# Canhbaochayrung.net
KiCad netlist of a schematic drawn in Altium Designer
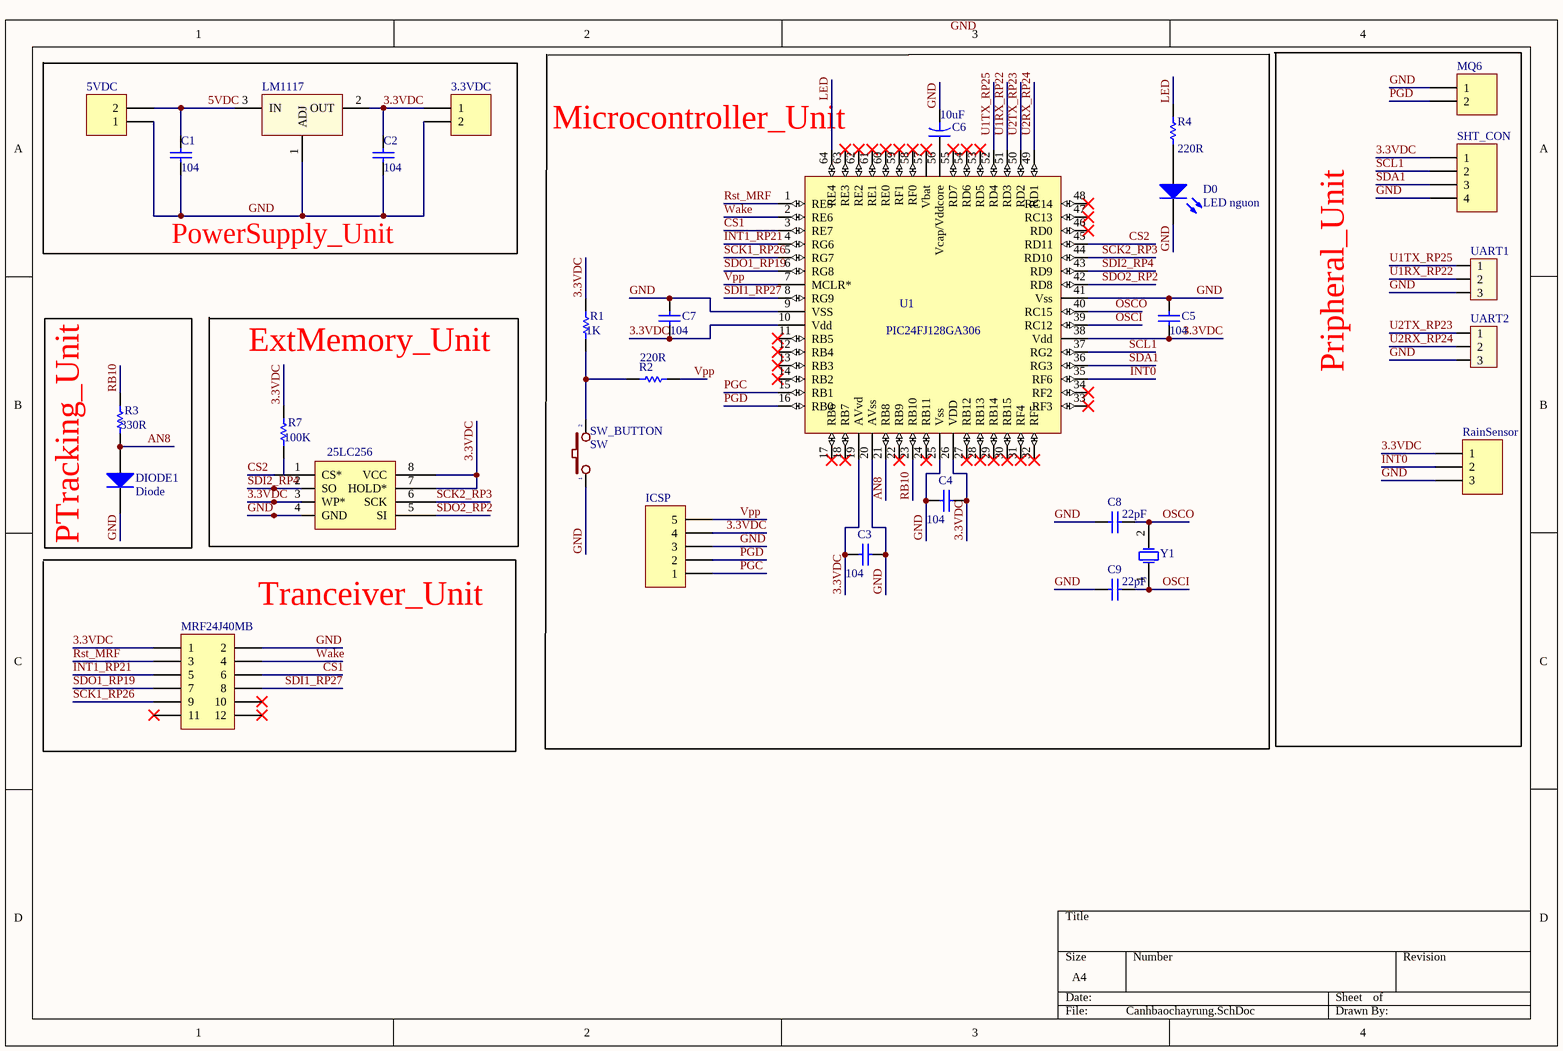
[diagram p0: Canhbaochayrung.SchDoc]

(export (version "E")
  (design (tool "Eeschema 10.0.6"))
  (components
    (comp (ref "3.3VDC")
      (value "Header 2")
      (footprint "HDR1X2")
      (description "Header, 2-Pin")
      (fields (field (name "PUBLISHER") "Altium Limited"))
      (libsource (lib "Miscellaneous Connectors") (part "Header 2"))
    )
    (comp (ref "5VDC")
      (value "Header 2")
      (footprint "HDR1X2")
      (description "Header, 2-Pin")
      (fields (field (name "PUBLISHER") "Altium Limited"))
      (libsource (lib "") (part "Header 2_1"))
    )
    (comp (ref "25LC256") (value "25LC256") (footprint "DIP-8") (libsource (lib "25LC256") (part "25LC256")))
    (comp (ref "C1")
      (value "104")
      (footprint "C0805")
      (description "Capacitor")
      (fields (field (name "Comment") "Cap") (field (name "PUBLISHER") "Altium Limited"))
      (libsource (lib "Miscellaneous Devices") (part "Cap"))
    )
    (comp (ref "C2")
      (value "104")
      (footprint "C0805")
      (description "Capacitor")
      (fields (field (name "Comment") "Cap") (field (name "PUBLISHER") "Altium Limited"))
      (libsource (lib "Miscellaneous Devices") (part "Cap"))
    )
    (comp (ref "C3")
      (value "104")
      (footprint "C0805")
      (description "Capacitor")
      (fields (field (name "Comment") "Cap") (field (name "PUBLISHER") "Altium Limited"))
      (libsource (lib "Miscellaneous Devices") (part "Cap"))
    )
    (comp (ref "C4")
      (value "104")
      (footprint "C0805")
      (description "Capacitor")
      (fields (field (name "Comment") "Cap") (field (name "PUBLISHER") "Altium Limited"))
      (libsource (lib "Miscellaneous Devices") (part "Cap"))
    )
    (comp (ref "C5")
      (value "104")
      (footprint "C0805")
      (description "Capacitor")
      (fields (field (name "Comment") "Cap") (field (name "PUBLISHER") "Altium Limited"))
      (libsource (lib "Miscellaneous Devices") (part "Cap"))
    )
    (comp (ref "C6")
      (value "10uF")
      (footprint "CAP P 6.3x5.4")
      (description "Capacitor")
      (fields (field (name "Comment") "Cap2") (field (name "PUBLISHER") "Altium Limited"))
      (libsource (lib "Miscellaneous Devices") (part "Cap2"))
    )
    (comp (ref "C7")
      (value "104")
      (footprint "C0805")
      (description "Capacitor")
      (fields (field (name "Comment") "Cap") (field (name "PUBLISHER") "Altium Limited"))
      (libsource (lib "Miscellaneous Devices") (part "Cap"))
    )
    (comp (ref "C8")
      (value "22pF")
      (footprint "SM-0805")
      (description "Capacitor")
      (fields (field (name "Comment") "Cap") (field (name "PUBLISHER") "Altium Limited"))
      (libsource (lib "Miscellaneous Devices") (part "Cap"))
    )
    (comp (ref "C9")
      (value "22pF")
      (footprint "SM-0805")
      (description "Capacitor")
      (fields (field (name "Comment") "Cap") (field (name "PUBLISHER") "Altium Limited"))
      (libsource (lib "Miscellaneous Devices") (part "Cap"))
    )
    (comp (ref "D0")
      (value "LED nguon")
      (footprint "LED3mm")
      (description "Typical INFRARED GaAs LED")
      (fields (field (name "PUBLISHER") "Altium Limited"))
      (libsource (lib "Miscellaneous Devices") (part "LED0"))
    )
    (comp (ref "DIODE1")
      (value "Diode")
      (footprint "DZ0.5A")
      (description "Default Diode")
      (fields (field (name "PUBLISHER") "Altium Limited"))
      (libsource (lib "Miscellaneous Devices") (part "Diode"))
    )
    (comp (ref "ICSP")
      (value "ICSP")
      (footprint "CON5")
      (description "Header, 5-Pin")
      (fields (field (name "PUBLISHER") "Altium Limited"))
      (libsource (lib "Miscellaneous Connectors") (part "Header 5"))
    )
    (comp (ref "LM1117")
      (value "LM317")
      (footprint "SOT223-4N")
      (description "Adj Voltage +1.2 -> +37V")
      (libsource (lib "syhaunguyen") (part "LM317"))
    )
    (comp (ref "MQ6")
      (value "MQ-6")
      (footprint "CON2")
      (description "Header, 2-Pin")
      (fields (field (name "PUBLISHER") "Altium Limited"))
      (libsource (lib "Miscellaneous Connectors") (part "Header 2"))
    )
    (comp (ref "MRF24J40MB")
      (value "Header 6X2")
      (footprint "MRF24J40MB_board_mini")
      (description "Header, 6-Pin, Dual row")
      (fields (field (name "PUBLISHER") "Altium Limited"))
      (libsource (lib "Miscellaneous Connectors") (part "Header 6X2"))
    )
    (comp (ref "R1")
      (value "1K")
      (footprint "C0805")
      (description "Resistor")
      (fields (field (name "Comment") "Res1") (field (name "PUBLISHER") "Altium Limited"))
      (libsource (lib "Miscellaneous Devices") (part "Res1"))
    )
    (comp (ref "R2")
      (value "220R")
      (footprint "C0805")
      (description "Resistor")
      (fields (field (name "Comment") "res") (field (name "PUBLISHER") "Altium Limited"))
      (libsource (lib "Miscellaneous Devices") (part "Res1"))
    )
    (comp (ref "R3")
      (value "330R")
      (footprint "C0805")
      (description "Resistor")
      (fields (field (name "Comment") "Res1") (field (name "PUBLISHER") "Altium Limited"))
      (libsource (lib "Miscellaneous Devices") (part "Res1"))
    )
    (comp (ref "R4")
      (value "220R")
      (footprint "C0805")
      (description "Resistor")
      (fields (field (name "Comment") "Res1") (field (name "PUBLISHER") "Altium Limited"))
      (libsource (lib "Miscellaneous Devices") (part "Res1"))
    )
    (comp (ref "R7")
      (value "100K")
      (footprint "C0805")
      (description "Semiconductor Resistor")
      (fields (field (name "Comment") "Res Semi") (field (name "PUBLISHER") "Altium Limited"))
      (libsource (lib "Miscellaneous Devices") (part "Res Semi"))
    )
    (comp (ref "RainSensor")
      (value "PIR module")
      (footprint "CON3")
      (description "Header, 3-Pin, Right Angle")
      (fields (field (name "PUBLISHER") "Altium Limited"))
      (libsource (lib "Miscellaneous Connectors") (part "Header 3H"))
    )
    (comp (ref "SHT_CON")
      (value "SHT10 conector")
      (footprint "CON4")
      (description "Header, 4-Pin")
      (fields (field (name "PUBLISHER") "Altium Limited"))
      (libsource (lib "Miscellaneous Connectors") (part "Header 4"))
    )
    (comp (ref "SW_BUTTON")
      (value "SW")
      (footprint "SW-2P-S")
      (description "Switch button 2 pin")
      (libsource (lib "syhaunguyen") (part "SW2"))
    )
    (comp (ref "U1")
      (value "PIC24FJ128GA306")
      (footprint "TQFP-PT64_N")
      (libsource (lib "Mylibbrary") (part "PIC24FJ128GA306"))
    )
    (comp (ref "UART1")
      (value "UART1")
      (footprint "CON3")
      (description "Connector 3")
      (libsource (lib "syhaunguyen") (part "Con3"))
    )
    (comp (ref "UART2")
      (value "UART2")
      (footprint "CON3")
      (description "Connector 3")
      (libsource (lib "syhaunguyen") (part "Con3"))
    )
    (comp (ref "Y1")
      (value "XTAL")
      (footprint "XT2")
      (description "Crystal Oscillator")
      (fields (field (name "PUBLISHER") "Altium Limited"))
      (libsource (lib "Miscellaneous Devices") (part "XTAL"))
    )
  )
  (nets
    (net (code "1") (name "/3.3VDC") (class "Default")
      (node (ref "25LC256") (pin "3") (pinfunction "WP*_3") (pintype "passive"))
      (node (ref "25LC256") (pin "7") (pinfunction "HOLD*_7") (pintype "passive"))
      (node (ref "25LC256") (pin "8") (pinfunction "VCC_8") (pintype "power_in"))
      (node (ref "3.3VDC") (pin "1") (pinfunction "1_1") (pintype "passive"))
      (node (ref "C2") (pin "2") (pinfunction "2_2") (pintype "passive"))
      (node (ref "C3") (pin "1") (pinfunction "1_1") (pintype "passive"))
      (node (ref "C4") (pin "2") (pinfunction "2_2") (pintype "passive"))
      (node (ref "C5") (pin "1") (pinfunction "1_1") (pintype "passive"))
      (node (ref "C7") (pin "1") (pinfunction "1_1") (pintype "passive"))
      (node (ref "ICSP") (pin "4") (pinfunction "4_4") (pintype "passive"))
      (node (ref "LM1117") (pin "2") (pinfunction "OUT_2") (pintype "passive"))
      (node (ref "MRF24J40MB") (pin "1") (pinfunction "1_1") (pintype "passive"))
      (node (ref "R1") (pin "2") (pinfunction "2_2") (pintype "passive"))
      (node (ref "R7") (pin "2") (pinfunction "2_2") (pintype "passive"))
      (node (ref "RainSensor") (pin "1") (pinfunction "1_1") (pintype "passive"))
      (node (ref "SHT_CON") (pin "1") (pinfunction "1_1") (pintype "passive"))
      (node (ref "U1") (pin "10") (pinfunction "Vdd_10") (pintype "passive"))
      (node (ref "U1") (pin "19") (pinfunction "AVvd_19") (pintype "power_in"))
      (node (ref "U1") (pin "26") (pinfunction "VDD_26") (pintype "power_in"))
      (node (ref "U1") (pin "38") (pinfunction "Vdd_38") (pintype "power_in"))
    )
    (net (code "2") (name "/5VDC") (class "Default")
      (node (ref "5VDC") (pin "2") (pinfunction "2_2") (pintype "passive"))
      (node (ref "C1") (pin "2") (pinfunction "2_2") (pintype "passive"))
      (node (ref "LM1117") (pin "3") (pinfunction "IN_3") (pintype "passive"))
    )
    (net (code "3") (name "/AN8") (class "Default")
      (node (ref "DIODE1") (pin "1") (pinfunction "A_1") (pintype "passive"))
      (node (ref "R3") (pin "1") (pinfunction "1_1") (pintype "passive"))
      (node (ref "U1") (pin "21") (pinfunction "RB8_21") (pintype "bidirectional"))
    )
    (net (code "4") (name "/CS1") (class "Default")
      (node (ref "MRF24J40MB") (pin "6") (pinfunction "6_6") (pintype "passive"))
      (node (ref "U1") (pin "3") (pinfunction "RE7_3") (pintype "bidirectional"))
    )
    (net (code "5") (name "/CS2") (class "Default")
      (node (ref "25LC256") (pin "1") (pinfunction "CS*_1") (pintype "passive"))
      (node (ref "U1") (pin "45") (pinfunction "RD11_45") (pintype "bidirectional"))
    )
    (net (code "6") (name "/GND") (class "Default")
      (node (ref "25LC256") (pin "4") (pinfunction "GND_4") (pintype "power_in"))
      (node (ref "3.3VDC") (pin "2") (pinfunction "2_2") (pintype "passive"))
      (node (ref "5VDC") (pin "1") (pinfunction "1_1") (pintype "passive"))
      (node (ref "C1") (pin "1") (pinfunction "1_1") (pintype "passive"))
      (node (ref "C2") (pin "1") (pinfunction "1_1") (pintype "passive"))
      (node (ref "C3") (pin "2") (pinfunction "2_2") (pintype "passive"))
      (node (ref "C4") (pin "1") (pinfunction "1_1") (pintype "passive"))
      (node (ref "C5") (pin "2") (pinfunction "2_2") (pintype "passive"))
      (node (ref "C6") (pin "2") (pinfunction "2_2") (pintype "passive"))
      (node (ref "C7") (pin "2") (pinfunction "2_2") (pintype "passive"))
      (node (ref "C8") (pin "1") (pinfunction "1_1") (pintype "passive"))
      (node (ref "C9") (pin "1") (pinfunction "1_1") (pintype "passive"))
      (node (ref "D0") (pin "2") (pinfunction "K_2") (pintype "passive"))
      (node (ref "DIODE1") (pin "2") (pinfunction "K_2") (pintype "passive"))
      (node (ref "ICSP") (pin "3") (pinfunction "3_3") (pintype "passive"))
      (node (ref "LM1117") (pin "1") (pinfunction "ADJ_1") (pintype "passive"))
      (node (ref "MQ6") (pin "1") (pinfunction "1_1") (pintype "passive"))
      (node (ref "MRF24J40MB") (pin "2") (pinfunction "2_2") (pintype "passive"))
      (node (ref "RainSensor") (pin "3") (pinfunction "3_3") (pintype "passive"))
      (node (ref "SHT_CON") (pin "4") (pinfunction "4_4") (pintype "passive"))
      (node (ref "SW_BUTTON") (pin "1") (pinfunction "1_1") (pintype "passive"))
      (node (ref "U1") (pin "20") (pinfunction "AVss_20") (pintype "power_in"))
      (node (ref "U1") (pin "25") (pinfunction "Vss_25") (pintype "power_in"))
      (node (ref "U1") (pin "41") (pinfunction "Vss_41") (pintype "power_in"))
      (node (ref "U1") (pin "9") (pinfunction "VSS_9") (pintype "power_in"))
      (node (ref "UART1") (pin "3") (pinfunction "3_3") (pintype "passive"))
      (node (ref "UART2") (pin "3") (pinfunction "3_3") (pintype "passive"))
    )
    (net (code "7") (name "/INT0") (class "Default")
      (node (ref "RainSensor") (pin "2") (pinfunction "2_2") (pintype "passive"))
      (node (ref "U1") (pin "35") (pinfunction "RF6_35") (pintype "bidirectional"))
    )
    (net (code "8") (name "/INT1_RP21") (class "Default")
      (node (ref "MRF24J40MB") (pin "5") (pinfunction "5_5") (pintype "passive"))
      (node (ref "U1") (pin "4") (pinfunction "RG6_4") (pintype "bidirectional"))
    )
    (net (code "9") (name "/LED") (class "Default")
      (node (ref "R4") (pin "2") (pinfunction "2_2") (pintype "passive"))
      (node (ref "U1") (pin "64") (pinfunction "RE4_64") (pintype "bidirectional"))
    )
    (net (code "10") (name "/OSCI") (class "Default")
      (node (ref "C9") (pin "2") (pinfunction "2_2") (pintype "passive"))
      (node (ref "U1") (pin "39") (pinfunction "RC12_39") (pintype "bidirectional"))
      (node (ref "Y1") (pin "1") (pinfunction "OSC1_1") (pintype "passive"))
    )
    (net (code "11") (name "/OSCO") (class "Default")
      (node (ref "C8") (pin "2") (pinfunction "2_2") (pintype "passive"))
      (node (ref "U1") (pin "40") (pinfunction "RC15_40") (pintype "bidirectional"))
      (node (ref "Y1") (pin "2") (pinfunction "OSC2_2") (pintype "passive"))
    )
    (net (code "12") (name "/PGC") (class "Default")
      (node (ref "ICSP") (pin "1") (pinfunction "1_1") (pintype "passive"))
      (node (ref "U1") (pin "15") (pinfunction "RB1_15") (pintype "bidirectional"))
    )
    (net (code "13") (name "/PGD") (class "Default")
      (node (ref "ICSP") (pin "2") (pinfunction "2_2") (pintype "passive"))
      (node (ref "MQ6") (pin "2") (pinfunction "2_2") (pintype "passive"))
      (node (ref "U1") (pin "16") (pinfunction "RB0_16") (pintype "bidirectional"))
    )
    (net (code "14") (name "/RB10") (class "Default")
      (node (ref "R3") (pin "2") (pinfunction "2_2") (pintype "passive"))
      (node (ref "U1") (pin "23") (pinfunction "RB10_23") (pintype "bidirectional"))
    )
    (net (code "15") (name "/Rst_MRF") (class "Default")
      (node (ref "MRF24J40MB") (pin "3") (pinfunction "3_3") (pintype "passive"))
      (node (ref "U1") (pin "1") (pinfunction "RE5_1") (pintype "bidirectional"))
    )
    (net (code "16") (name "/SCK1_RP26") (class "Default")
      (node (ref "MRF24J40MB") (pin "9") (pinfunction "9_9") (pintype "passive"))
      (node (ref "U1") (pin "5") (pinfunction "RG7_5") (pintype "bidirectional"))
    )
    (net (code "17") (name "/SCK2_RP3") (class "Default")
      (node (ref "25LC256") (pin "6") (pinfunction "SCK_6") (pintype "passive"))
      (node (ref "U1") (pin "44") (pinfunction "RD10_44") (pintype "bidirectional"))
    )
    (net (code "18") (name "/SCL1") (class "Default")
      (node (ref "SHT_CON") (pin "2") (pinfunction "2_2") (pintype "passive"))
      (node (ref "U1") (pin "37") (pinfunction "RG2_37") (pintype "bidirectional"))
    )
    (net (code "19") (name "/SDA1") (class "Default")
      (node (ref "SHT_CON") (pin "3") (pinfunction "3_3") (pintype "passive"))
      (node (ref "U1") (pin "36") (pinfunction "RG3_36") (pintype "bidirectional"))
    )
    (net (code "20") (name "/SDI1_RP27") (class "Default")
      (node (ref "MRF24J40MB") (pin "8") (pinfunction "8_8") (pintype "passive"))
      (node (ref "U1") (pin "8") (pinfunction "RG9_8") (pintype "bidirectional"))
    )
    (net (code "21") (name "/SDI2_RP4") (class "Default")
      (node (ref "25LC256") (pin "2") (pinfunction "SO_2") (pintype "passive"))
      (node (ref "U1") (pin "43") (pinfunction "RD9_43") (pintype "bidirectional"))
    )
    (net (code "22") (name "/SDO1_RP19") (class "Default")
      (node (ref "MRF24J40MB") (pin "7") (pinfunction "7_7") (pintype "passive"))
      (node (ref "U1") (pin "6") (pinfunction "RG8_6") (pintype "bidirectional"))
    )
    (net (code "23") (name "/SDO2_RP2") (class "Default")
      (node (ref "25LC256") (pin "5") (pinfunction "SI_5") (pintype "passive"))
      (node (ref "U1") (pin "42") (pinfunction "RD8_42") (pintype "bidirectional"))
    )
    (net (code "24") (name "/U1RX_RP22") (class "Default")
      (node (ref "U1") (pin "51") (pinfunction "RD3_51") (pintype "bidirectional"))
      (node (ref "UART1") (pin "2") (pinfunction "2_2") (pintype "passive"))
    )
    (net (code "25") (name "/U1TX_RP25") (class "Default")
      (node (ref "U1") (pin "52") (pinfunction "RD4_52") (pintype "bidirectional"))
      (node (ref "UART1") (pin "1") (pinfunction "1_1") (pintype "passive"))
    )
    (net (code "26") (name "/U2RX_RP24") (class "Default")
      (node (ref "U1") (pin "49") (pinfunction "RD1_49") (pintype "bidirectional"))
      (node (ref "UART2") (pin "2") (pinfunction "2_2") (pintype "passive"))
    )
    (net (code "27") (name "/U2TX_RP23") (class "Default")
      (node (ref "U1") (pin "50") (pinfunction "RD2_50") (pintype "bidirectional"))
      (node (ref "UART2") (pin "1") (pinfunction "1_1") (pintype "passive"))
    )
    (net (code "28") (name "/Vpp") (class "Default")
      (node (ref "ICSP") (pin "5") (pinfunction "5_5") (pintype "passive"))
      (node (ref "R2") (pin "2") (pinfunction "2_2") (pintype "passive"))
      (node (ref "U1") (pin "7") (pinfunction "MCLR*_7") (pintype "passive"))
    )
    (net (code "29") (name "/Wake") (class "Default")
      (node (ref "MRF24J40MB") (pin "4") (pinfunction "4_4") (pintype "passive"))
      (node (ref "U1") (pin "2") (pinfunction "RE6_2") (pintype "bidirectional"))
    )
    (net (code "30") (name "Net-(D0-A)") (class "Default")
      (node (ref "D0") (pin "1") (pinfunction "A_1") (pintype "passive"))
      (node (ref "R4") (pin "1") (pinfunction "1_1") (pintype "passive"))
    )
    (net (code "31") (name "Net-(R1-Pad1)") (class "Default")
      (node (ref "R1") (pin "1") (pinfunction "1_1") (pintype "passive"))
      (node (ref "R2") (pin "1") (pinfunction "1_1") (pintype "passive"))
      (node (ref "SW_BUTTON") (pin "2") (pinfunction "2_2") (pintype "passive"))
    )
    (net (code "32") (name "Net-(U1-Vcap{slash}Vddcore)") (class "Default")
      (node (ref "C6") (pin "1") (pinfunction "1_1") (pintype "passive"))
      (node (ref "U1") (pin "56") (pinfunction "Vcap/Vddcore_56") (pintype "power_in"))
    )
    (net (code "33") (name "unconnected-(MRF24J40MB-Pad10)") (class "Default")
      (node (ref "MRF24J40MB") (pin "10") (pinfunction "10_10") (pintype "passive+no_connect"))
    )
    (net (code "34") (name "unconnected-(MRF24J40MB-Pad11)") (class "Default")
      (node (ref "MRF24J40MB") (pin "11") (pinfunction "11_11") (pintype "passive+no_connect"))
    )
    (net (code "35") (name "unconnected-(MRF24J40MB-Pad12)") (class "Default")
      (node (ref "MRF24J40MB") (pin "12") (pinfunction "12_12") (pintype "passive+no_connect"))
    )
    (net (code "36") (name "unconnected-(R7-Pad1)") (class "Default")
      (node (ref "R7") (pin "1") (pinfunction "1_1") (pintype "passive"))
    )
    (net (code "37") (name "unconnected-(U1-RB2-Pad14)") (class "Default")
      (node (ref "U1") (pin "14") (pinfunction "RB2_14") (pintype "bidirectional+no_connect"))
    )
    (net (code "38") (name "unconnected-(U1-RB3-Pad13)") (class "Default")
      (node (ref "U1") (pin "13") (pinfunction "RB3_13") (pintype "bidirectional+no_connect"))
    )
    (net (code "39") (name "unconnected-(U1-RB4-Pad12)") (class "Default")
      (node (ref "U1") (pin "12") (pinfunction "RB4_12") (pintype "bidirectional+no_connect"))
    )
    (net (code "40") (name "unconnected-(U1-RB5-Pad11)") (class "Default")
      (node (ref "U1") (pin "11") (pinfunction "RB5_11") (pintype "bidirectional+no_connect"))
    )
    (net (code "41") (name "unconnected-(U1-RB6-Pad17)") (class "Default")
      (node (ref "U1") (pin "17") (pinfunction "RB6_17") (pintype "bidirectional+no_connect"))
    )
    (net (code "42") (name "unconnected-(U1-RB7-Pad18)") (class "Default")
      (node (ref "U1") (pin "18") (pinfunction "RB7_18") (pintype "bidirectional+no_connect"))
    )
    (net (code "43") (name "unconnected-(U1-RB9-Pad22)") (class "Default")
      (node (ref "U1") (pin "22") (pinfunction "RB9_22") (pintype "bidirectional+no_connect"))
    )
    (net (code "44") (name "unconnected-(U1-RB11-Pad24)") (class "Default")
      (node (ref "U1") (pin "24") (pinfunction "RB11_24") (pintype "bidirectional+no_connect"))
    )
    (net (code "45") (name "unconnected-(U1-RB12-Pad27)") (class "Default")
      (node (ref "U1") (pin "27") (pinfunction "RB12_27") (pintype "bidirectional+no_connect"))
    )
    (net (code "46") (name "unconnected-(U1-RB13-Pad28)") (class "Default")
      (node (ref "U1") (pin "28") (pinfunction "RB13_28") (pintype "bidirectional+no_connect"))
    )
    (net (code "47") (name "unconnected-(U1-RB14-Pad29)") (class "Default")
      (node (ref "U1") (pin "29") (pinfunction "RB14_29") (pintype "bidirectional+no_connect"))
    )
    (net (code "48") (name "unconnected-(U1-RB15-Pad30)") (class "Default")
      (node (ref "U1") (pin "30") (pinfunction "RB15_30") (pintype "bidirectional+no_connect"))
    )
    (net (code "49") (name "unconnected-(U1-RC13-Pad47)") (class "Default")
      (node (ref "U1") (pin "47") (pinfunction "RC13_47") (pintype "bidirectional+no_connect"))
    )
    (net (code "50") (name "unconnected-(U1-RC14-Pad48)") (class "Default")
      (node (ref "U1") (pin "48") (pinfunction "RC14_48") (pintype "bidirectional+no_connect"))
    )
    (net (code "51") (name "unconnected-(U1-RD0-Pad46)") (class "Default")
      (node (ref "U1") (pin "46") (pinfunction "RD0_46") (pintype "bidirectional+no_connect"))
    )
    (net (code "52") (name "unconnected-(U1-RD5-Pad53)") (class "Default")
      (node (ref "U1") (pin "53") (pinfunction "RD5_53") (pintype "bidirectional+no_connect"))
    )
    (net (code "53") (name "unconnected-(U1-RD6-Pad54)") (class "Default")
      (node (ref "U1") (pin "54") (pinfunction "RD6_54") (pintype "bidirectional+no_connect"))
    )
    (net (code "54") (name "unconnected-(U1-RD7-Pad55)") (class "Default")
      (node (ref "U1") (pin "55") (pinfunction "RD7_55") (pintype "bidirectional+no_connect"))
    )
    (net (code "55") (name "unconnected-(U1-RE0-Pad60)") (class "Default")
      (node (ref "U1") (pin "60") (pinfunction "RE0_60") (pintype "bidirectional+no_connect"))
    )
    (net (code "56") (name "unconnected-(U1-RE1-Pad61)") (class "Default")
      (node (ref "U1") (pin "61") (pinfunction "RE1_61") (pintype "bidirectional+no_connect"))
    )
    (net (code "57") (name "unconnected-(U1-RE2-Pad62)") (class "Default")
      (node (ref "U1") (pin "62") (pinfunction "RE2_62") (pintype "bidirectional+no_connect"))
    )
    (net (code "58") (name "unconnected-(U1-RE3-Pad63)") (class "Default")
      (node (ref "U1") (pin "63") (pinfunction "RE3_63") (pintype "bidirectional+no_connect"))
    )
    (net (code "59") (name "unconnected-(U1-RF0-Pad58)") (class "Default")
      (node (ref "U1") (pin "58") (pinfunction "RF0_58") (pintype "bidirectional+no_connect"))
    )
    (net (code "60") (name "unconnected-(U1-RF1-Pad59)") (class "Default")
      (node (ref "U1") (pin "59") (pinfunction "RF1_59") (pintype "bidirectional+no_connect"))
    )
    (net (code "61") (name "unconnected-(U1-RF2-Pad34)") (class "Default")
      (node (ref "U1") (pin "34") (pinfunction "RF2_34") (pintype "bidirectional+no_connect"))
    )
    (net (code "62") (name "unconnected-(U1-RF3-Pad33)") (class "Default")
      (node (ref "U1") (pin "33") (pinfunction "RF3_33") (pintype "bidirectional+no_connect"))
    )
    (net (code "63") (name "unconnected-(U1-RF4-Pad31)") (class "Default")
      (node (ref "U1") (pin "31") (pinfunction "RF4_31") (pintype "bidirectional+no_connect"))
    )
    (net (code "64") (name "unconnected-(U1-RF5-Pad32)") (class "Default")
      (node (ref "U1") (pin "32") (pinfunction "RF5_32") (pintype "bidirectional+no_connect"))
    )
    (net (code "65") (name "unconnected-(U1-Vbat-Pad57)") (class "Default")
      (node (ref "U1") (pin "57") (pinfunction "Vbat_57") (pintype "power_in+no_connect"))
    )
  )
)
